# untitled6.net
KiCad netlist of a schematic drawn in EAGLE
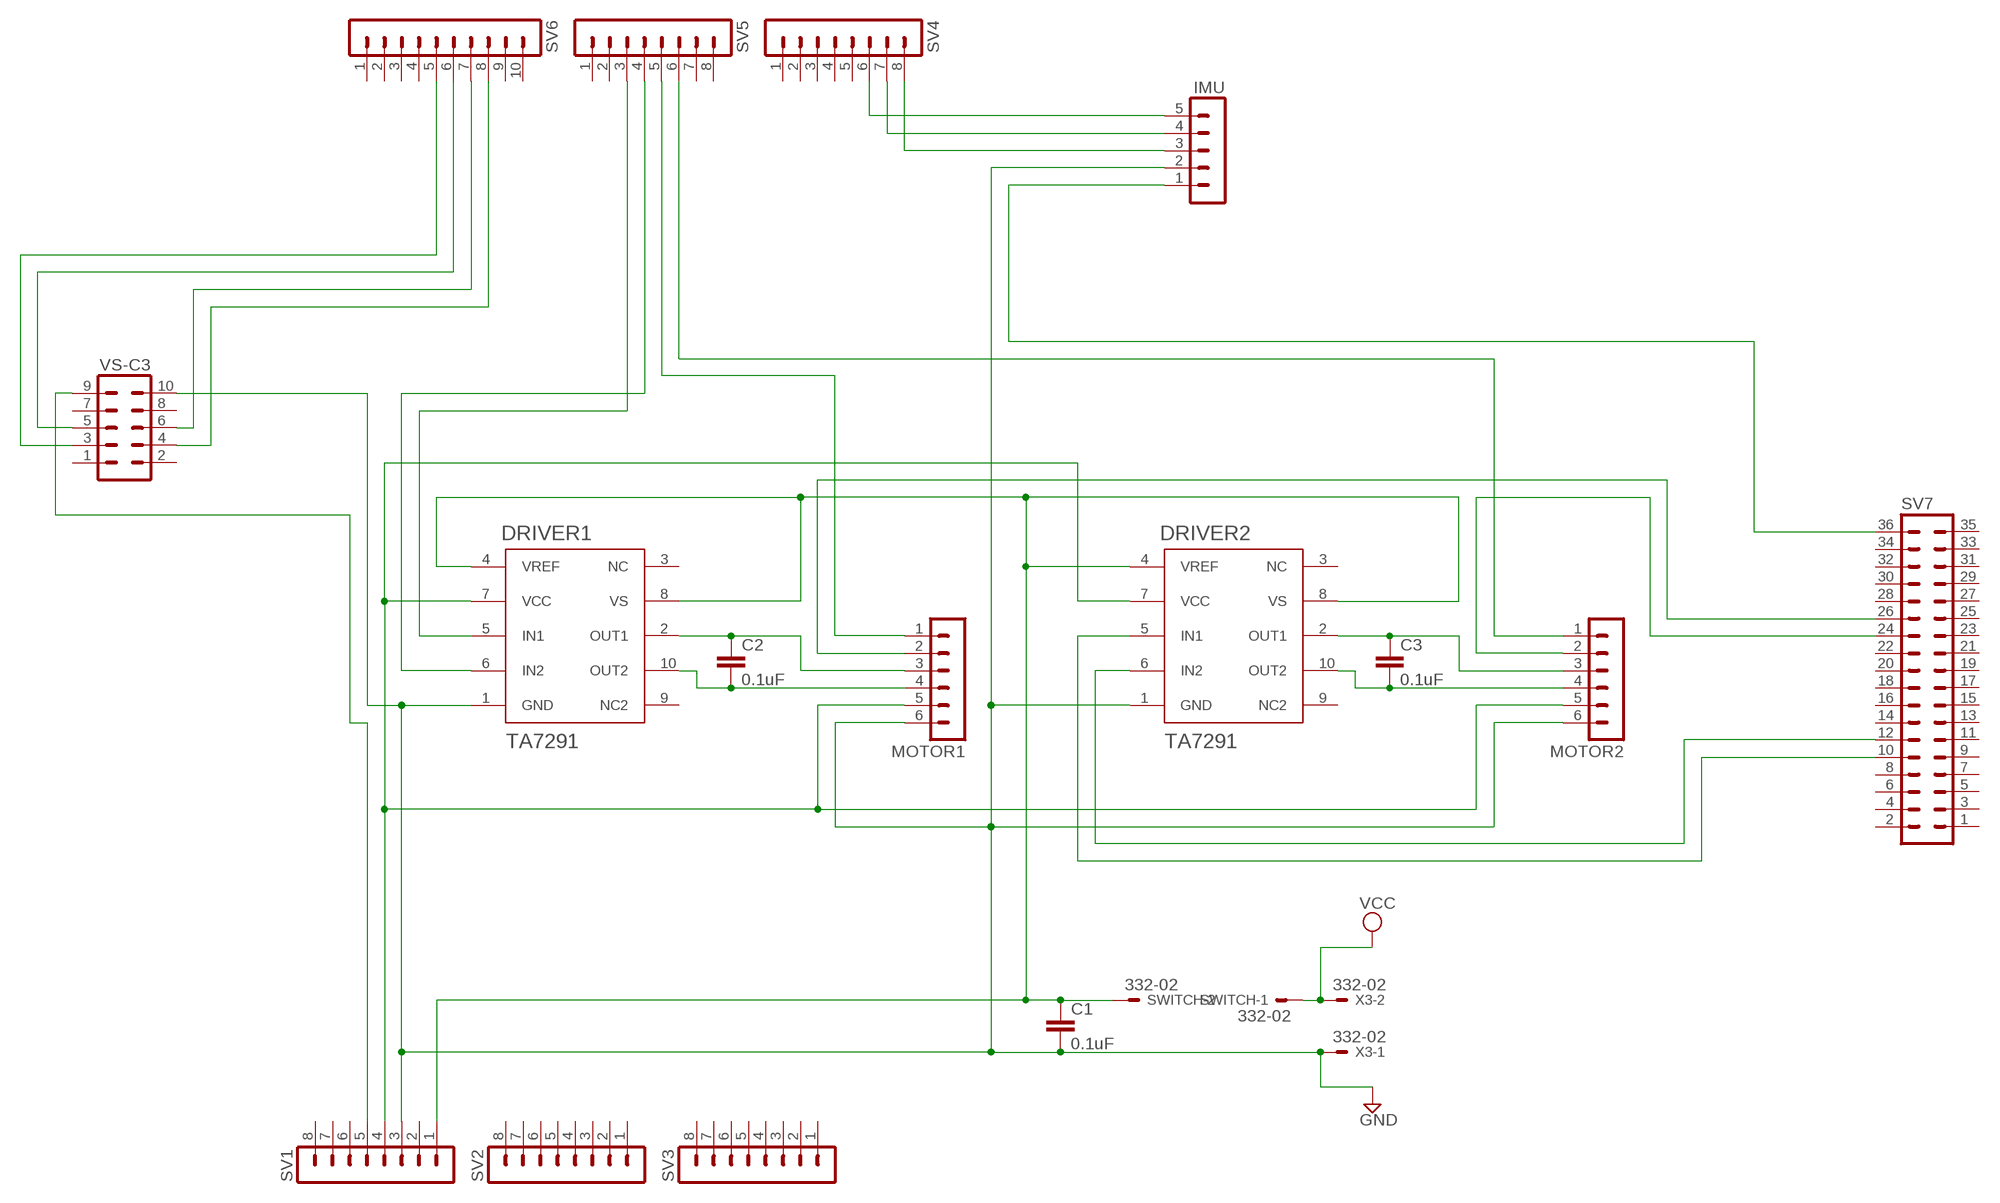
[diagram p0: schematic, sheet 1]

(export (version "E")
  (design (tool "Eeschema 10.0.6"))
  (components
    (comp (ref "C1")
      (value "0.1uF")
      (footprint "eagle-import:C5B2.5")
      (libsource (lib "eagle-import") (part "C5/2.5"))
    )
    (comp (ref "C2")
      (value "0.1uF")
      (footprint "eagle-import:C5B2.5")
      (libsource (lib "eagle-import") (part "C5/2.5"))
    )
    (comp (ref "C3")
      (value "0.1uF")
      (footprint "eagle-import:C5B2.5")
      (libsource (lib "eagle-import") (part "C5/2.5"))
    )
    (comp (ref "DRIVER1")
      (value "TA7291")
      (footprint "eagle-import:HSIP10")
      (libsource (lib "eagle-import") (part "TA7291"))
    )
    (comp (ref "DRIVER2")
      (value "TA7291")
      (footprint "eagle-import:HSIP10")
      (libsource (lib "eagle-import") (part "TA7291"))
    )
    (comp (ref "IMU")
      (value "MA05-1")
      (footprint "eagle-import:MA05-1")
      (libsource (lib "eagle-import") (part "MA05-1"))
    )
    (comp (ref "MOTOR1")
      (value "MA06-1")
      (footprint "eagle-import:MA06-1")
      (libsource (lib "eagle-import") (part "MA06-1"))
    )
    (comp (ref "MOTOR2")
      (value "MA06-1")
      (footprint "eagle-import:MA06-1")
      (libsource (lib "eagle-import") (part "MA06-1"))
    )
    (comp (ref "SV1")
      (value "MA08-1")
      (footprint "eagle-import:MA08-1")
      (libsource (lib "eagle-import") (part "MA08-1"))
    )
    (comp (ref "SV2")
      (value "MA08-1")
      (footprint "eagle-import:MA08-1")
      (libsource (lib "eagle-import") (part "MA08-1"))
    )
    (comp (ref "SV3")
      (value "MA08-1")
      (footprint "eagle-import:MA08-1")
      (libsource (lib "eagle-import") (part "MA08-1"))
    )
    (comp (ref "SV4")
      (value "MA08-1")
      (footprint "eagle-import:MA08-1")
      (libsource (lib "eagle-import") (part "MA08-1"))
    )
    (comp (ref "SV5")
      (value "MA08-1")
      (footprint "eagle-import:MA08-1")
      (libsource (lib "eagle-import") (part "MA08-1"))
    )
    (comp (ref "SV6")
      (value "MA10-1")
      (footprint "eagle-import:MA10-1")
      (libsource (lib "eagle-import") (part "MA10-1"))
    )
    (comp (ref "SV7")
      (value "MA18-2")
      (footprint "eagle-import:MA18-2")
      (libsource (lib "eagle-import") (part "MA18-2"))
    )
    (comp (ref "SWITCH")
      (value "332-02")
      (footprint "eagle-import:332-02")
      (libsource (lib "eagle-import") (part "332-02"))
    )
    (comp (ref "VS-C3")
      (value "MA05-2")
      (footprint "eagle-import:MA05-2")
      (libsource (lib "eagle-import") (part "MA05-2"))
    )
    (comp (ref "X3")
      (value "332-02")
      (footprint "eagle-import:332-02")
      (libsource (lib "eagle-import") (part "332-02"))
    )
  )
  (nets
    (net (code "1") (name "GND") (class "Default")
      (node (ref "C1") (pin "2") (pinfunction "2_2") (pintype "passive"))
      (node (ref "DRIVER1") (pin "1") (pinfunction "GND_1") (pintype "bidirectional"))
      (node (ref "DRIVER2") (pin "1") (pinfunction "GND_1") (pintype "bidirectional"))
      (node (ref "IMU") (pin "2") (pinfunction "2_2") (pintype "passive"))
      (node (ref "MOTOR1") (pin "6") (pinfunction "6_6") (pintype "passive"))
      (node (ref "MOTOR2") (pin "6") (pinfunction "6_6") (pintype "passive"))
      (node (ref "SV1") (pin "3") (pinfunction "3_3") (pintype "passive"))
      (node (ref "VS-C3") (pin "10") (pinfunction "10_10") (pintype "passive"))
      (node (ref "X3") (pin "1") (pinfunction "S_1") (pintype "passive"))
    )
    (net (code "2") (name "Net-(DRIVER1-IN1)") (class "Default")
      (node (ref "DRIVER1") (pin "5") (pinfunction "IN1_5") (pintype "bidirectional"))
      (node (ref "SV5") (pin "3") (pinfunction "3_3") (pintype "passive"))
    )
    (net (code "3") (name "Net-(DRIVER1-IN2)") (class "Default")
      (node (ref "DRIVER1") (pin "6") (pinfunction "IN2_6") (pintype "bidirectional"))
      (node (ref "SV5") (pin "4") (pinfunction "4_4") (pintype "passive"))
    )
    (net (code "4") (name "Net-(DRIVER1-OUT1)") (class "Default")
      (node (ref "C2") (pin "1") (pinfunction "1_1") (pintype "passive"))
      (node (ref "DRIVER1") (pin "2") (pinfunction "OUT1_2") (pintype "bidirectional"))
      (node (ref "MOTOR1") (pin "3") (pinfunction "3_3") (pintype "passive"))
    )
    (net (code "5") (name "Net-(DRIVER1-OUT2)") (class "Default")
      (node (ref "C2") (pin "2") (pinfunction "2_2") (pintype "passive"))
      (node (ref "DRIVER1") (pin "10") (pinfunction "OUT2_10") (pintype "bidirectional"))
      (node (ref "MOTOR1") (pin "4") (pinfunction "4_4") (pintype "passive"))
    )
    (net (code "6") (name "Net-(DRIVER1-VCC)") (class "Default")
      (node (ref "DRIVER1") (pin "7") (pinfunction "VCC_7") (pintype "bidirectional"))
      (node (ref "DRIVER2") (pin "7") (pinfunction "VCC_7") (pintype "bidirectional"))
      (node (ref "MOTOR1") (pin "5") (pinfunction "5_5") (pintype "passive"))
      (node (ref "MOTOR2") (pin "5") (pinfunction "5_5") (pintype "passive"))
      (node (ref "SV1") (pin "4") (pinfunction "4_4") (pintype "passive"))
    )
    (net (code "7") (name "Net-(DRIVER1-VREF)") (class "Default")
      (node (ref "C1") (pin "1") (pinfunction "1_1") (pintype "passive"))
      (node (ref "DRIVER1") (pin "4") (pinfunction "VREF_4") (pintype "bidirectional"))
      (node (ref "DRIVER1") (pin "8") (pinfunction "VS_8") (pintype "bidirectional"))
      (node (ref "DRIVER2") (pin "4") (pinfunction "VREF_4") (pintype "bidirectional"))
      (node (ref "DRIVER2") (pin "8") (pinfunction "VS_8") (pintype "bidirectional"))
      (node (ref "SV1") (pin "1") (pinfunction "1_1") (pintype "passive"))
      (node (ref "SWITCH") (pin "2") (pinfunction "S_2") (pintype "passive"))
    )
    (net (code "8") (name "Net-(DRIVER2-IN1)") (class "Default")
      (node (ref "DRIVER2") (pin "5") (pinfunction "IN1_5") (pintype "bidirectional"))
      (node (ref "SV7") (pin "10") (pinfunction "10_10") (pintype "passive"))
    )
    (net (code "9") (name "Net-(DRIVER2-IN2)") (class "Default")
      (node (ref "DRIVER2") (pin "6") (pinfunction "IN2_6") (pintype "bidirectional"))
      (node (ref "SV7") (pin "12") (pinfunction "12_12") (pintype "passive"))
    )
    (net (code "10") (name "Net-(DRIVER2-OUT1)") (class "Default")
      (node (ref "C3") (pin "1") (pinfunction "1_1") (pintype "passive"))
      (node (ref "DRIVER2") (pin "2") (pinfunction "OUT1_2") (pintype "bidirectional"))
      (node (ref "MOTOR2") (pin "3") (pinfunction "3_3") (pintype "passive"))
    )
    (net (code "11") (name "Net-(DRIVER2-OUT2)") (class "Default")
      (node (ref "C3") (pin "2") (pinfunction "2_2") (pintype "passive"))
      (node (ref "DRIVER2") (pin "10") (pinfunction "OUT2_10") (pintype "bidirectional"))
      (node (ref "MOTOR2") (pin "4") (pinfunction "4_4") (pintype "passive"))
    )
    (net (code "12") (name "Net-(IMU-Pad1)") (class "Default")
      (node (ref "IMU") (pin "1") (pinfunction "1_1") (pintype "passive"))
      (node (ref "SV7") (pin "36") (pinfunction "36_36") (pintype "passive"))
    )
    (net (code "13") (name "Net-(IMU-Pad3)") (class "Default")
      (node (ref "IMU") (pin "3") (pinfunction "3_3") (pintype "passive"))
      (node (ref "SV4") (pin "8") (pinfunction "8_8") (pintype "passive"))
    )
    (net (code "14") (name "Net-(IMU-Pad4)") (class "Default")
      (node (ref "IMU") (pin "4") (pinfunction "4_4") (pintype "passive"))
      (node (ref "SV4") (pin "7") (pinfunction "7_7") (pintype "passive"))
    )
    (net (code "15") (name "Net-(IMU-Pad5)") (class "Default")
      (node (ref "IMU") (pin "5") (pinfunction "5_5") (pintype "passive"))
      (node (ref "SV4") (pin "6") (pinfunction "6_6") (pintype "passive"))
    )
    (net (code "16") (name "Net-(MOTOR1-Pad1)") (class "Default")
      (node (ref "MOTOR1") (pin "1") (pinfunction "1_1") (pintype "passive"))
      (node (ref "SV5") (pin "5") (pinfunction "5_5") (pintype "passive"))
    )
    (net (code "17") (name "Net-(MOTOR1-Pad2)") (class "Default")
      (node (ref "MOTOR1") (pin "2") (pinfunction "2_2") (pintype "passive"))
      (node (ref "SV7") (pin "26") (pinfunction "26_26") (pintype "passive"))
    )
    (net (code "18") (name "Net-(MOTOR2-Pad1)") (class "Default")
      (node (ref "MOTOR2") (pin "1") (pinfunction "1_1") (pintype "passive"))
      (node (ref "SV5") (pin "6") (pinfunction "6_6") (pintype "passive"))
    )
    (net (code "19") (name "Net-(MOTOR2-Pad2)") (class "Default")
      (node (ref "MOTOR2") (pin "2") (pinfunction "2_2") (pintype "passive"))
      (node (ref "SV7") (pin "24") (pinfunction "24_24") (pintype "passive"))
    )
    (net (code "20") (name "Net-(SV1-Pad5)") (class "Default")
      (node (ref "SV1") (pin "5") (pinfunction "5_5") (pintype "passive"))
      (node (ref "VS-C3") (pin "9") (pinfunction "9_9") (pintype "passive"))
    )
    (net (code "21") (name "Net-(SV6-Pad5)") (class "Default")
      (node (ref "SV6") (pin "5") (pinfunction "5_5") (pintype "passive"))
      (node (ref "VS-C3") (pin "3") (pinfunction "3_3") (pintype "passive"))
    )
    (net (code "22") (name "Net-(SV6-Pad6)") (class "Default")
      (node (ref "SV6") (pin "6") (pinfunction "6_6") (pintype "passive"))
      (node (ref "VS-C3") (pin "5") (pinfunction "5_5") (pintype "passive"))
    )
    (net (code "23") (name "Net-(SV6-Pad7)") (class "Default")
      (node (ref "SV6") (pin "7") (pinfunction "7_7") (pintype "passive"))
      (node (ref "VS-C3") (pin "6") (pinfunction "6_6") (pintype "passive"))
    )
    (net (code "24") (name "Net-(SV6-Pad8)") (class "Default")
      (node (ref "SV6") (pin "8") (pinfunction "8_8") (pintype "passive"))
      (node (ref "VS-C3") (pin "4") (pinfunction "4_4") (pintype "passive"))
    )
    (net (code "25") (name "VCC") (class "Default")
      (node (ref "SWITCH") (pin "1") (pinfunction "S_1") (pintype "passive"))
      (node (ref "X3") (pin "2") (pinfunction "S_2") (pintype "passive"))
    )
    (net (code "26") (name "unconnected-(DRIVER1-NC-Pad3)") (class "Default")
      (node (ref "DRIVER1") (pin "3") (pinfunction "NC_3") (pintype "bidirectional"))
    )
    (net (code "27") (name "unconnected-(DRIVER1-NC2-Pad9)") (class "Default")
      (node (ref "DRIVER1") (pin "9") (pinfunction "NC2_9") (pintype "bidirectional"))
    )
    (net (code "28") (name "unconnected-(DRIVER2-NC-Pad3)") (class "Default")
      (node (ref "DRIVER2") (pin "3") (pinfunction "NC_3") (pintype "bidirectional"))
    )
    (net (code "29") (name "unconnected-(DRIVER2-NC2-Pad9)") (class "Default")
      (node (ref "DRIVER2") (pin "9") (pinfunction "NC2_9") (pintype "bidirectional"))
    )
    (net (code "30") (name "unconnected-(SV1-Pad2)") (class "Default")
      (node (ref "SV1") (pin "2") (pinfunction "2_2") (pintype "passive"))
    )
    (net (code "31") (name "unconnected-(SV1-Pad6)") (class "Default")
      (node (ref "SV1") (pin "6") (pinfunction "6_6") (pintype "passive"))
    )
    (net (code "32") (name "unconnected-(SV1-Pad7)") (class "Default")
      (node (ref "SV1") (pin "7") (pinfunction "7_7") (pintype "passive"))
    )
    (net (code "33") (name "unconnected-(SV1-Pad8)") (class "Default")
      (node (ref "SV1") (pin "8") (pinfunction "8_8") (pintype "passive"))
    )
    (net (code "34") (name "unconnected-(SV2-Pad1)") (class "Default")
      (node (ref "SV2") (pin "1") (pinfunction "1_1") (pintype "passive"))
    )
    (net (code "35") (name "unconnected-(SV2-Pad2)") (class "Default")
      (node (ref "SV2") (pin "2") (pinfunction "2_2") (pintype "passive"))
    )
    (net (code "36") (name "unconnected-(SV2-Pad3)") (class "Default")
      (node (ref "SV2") (pin "3") (pinfunction "3_3") (pintype "passive"))
    )
    (net (code "37") (name "unconnected-(SV2-Pad4)") (class "Default")
      (node (ref "SV2") (pin "4") (pinfunction "4_4") (pintype "passive"))
    )
    (net (code "38") (name "unconnected-(SV2-Pad5)") (class "Default")
      (node (ref "SV2") (pin "5") (pinfunction "5_5") (pintype "passive"))
    )
    (net (code "39") (name "unconnected-(SV2-Pad6)") (class "Default")
      (node (ref "SV2") (pin "6") (pinfunction "6_6") (pintype "passive"))
    )
    (net (code "40") (name "unconnected-(SV2-Pad7)") (class "Default")
      (node (ref "SV2") (pin "7") (pinfunction "7_7") (pintype "passive"))
    )
    (net (code "41") (name "unconnected-(SV2-Pad8)") (class "Default")
      (node (ref "SV2") (pin "8") (pinfunction "8_8") (pintype "passive"))
    )
    (net (code "42") (name "unconnected-(SV3-Pad1)") (class "Default")
      (node (ref "SV3") (pin "1") (pinfunction "1_1") (pintype "passive"))
    )
    (net (code "43") (name "unconnected-(SV3-Pad2)") (class "Default")
      (node (ref "SV3") (pin "2") (pinfunction "2_2") (pintype "passive"))
    )
    (net (code "44") (name "unconnected-(SV3-Pad3)") (class "Default")
      (node (ref "SV3") (pin "3") (pinfunction "3_3") (pintype "passive"))
    )
    (net (code "45") (name "unconnected-(SV3-Pad4)") (class "Default")
      (node (ref "SV3") (pin "4") (pinfunction "4_4") (pintype "passive"))
    )
    (net (code "46") (name "unconnected-(SV3-Pad5)") (class "Default")
      (node (ref "SV3") (pin "5") (pinfunction "5_5") (pintype "passive"))
    )
    (net (code "47") (name "unconnected-(SV3-Pad6)") (class "Default")
      (node (ref "SV3") (pin "6") (pinfunction "6_6") (pintype "passive"))
    )
    (net (code "48") (name "unconnected-(SV3-Pad7)") (class "Default")
      (node (ref "SV3") (pin "7") (pinfunction "7_7") (pintype "passive"))
    )
    (net (code "49") (name "unconnected-(SV3-Pad8)") (class "Default")
      (node (ref "SV3") (pin "8") (pinfunction "8_8") (pintype "passive"))
    )
    (net (code "50") (name "unconnected-(SV4-Pad1)") (class "Default")
      (node (ref "SV4") (pin "1") (pinfunction "1_1") (pintype "passive"))
    )
    (net (code "51") (name "unconnected-(SV4-Pad2)") (class "Default")
      (node (ref "SV4") (pin "2") (pinfunction "2_2") (pintype "passive"))
    )
    (net (code "52") (name "unconnected-(SV4-Pad3)") (class "Default")
      (node (ref "SV4") (pin "3") (pinfunction "3_3") (pintype "passive"))
    )
    (net (code "53") (name "unconnected-(SV4-Pad4)") (class "Default")
      (node (ref "SV4") (pin "4") (pinfunction "4_4") (pintype "passive"))
    )
    (net (code "54") (name "unconnected-(SV4-Pad5)") (class "Default")
      (node (ref "SV4") (pin "5") (pinfunction "5_5") (pintype "passive"))
    )
    (net (code "55") (name "unconnected-(SV5-Pad1)") (class "Default")
      (node (ref "SV5") (pin "1") (pinfunction "1_1") (pintype "passive"))
    )
    (net (code "56") (name "unconnected-(SV5-Pad2)") (class "Default")
      (node (ref "SV5") (pin "2") (pinfunction "2_2") (pintype "passive"))
    )
    (net (code "57") (name "unconnected-(SV5-Pad7)") (class "Default")
      (node (ref "SV5") (pin "7") (pinfunction "7_7") (pintype "passive"))
    )
    (net (code "58") (name "unconnected-(SV5-Pad8)") (class "Default")
      (node (ref "SV5") (pin "8") (pinfunction "8_8") (pintype "passive"))
    )
    (net (code "59") (name "unconnected-(SV6-Pad1)") (class "Default")
      (node (ref "SV6") (pin "1") (pinfunction "1_1") (pintype "passive"))
    )
    (net (code "60") (name "unconnected-(SV6-Pad2)") (class "Default")
      (node (ref "SV6") (pin "2") (pinfunction "2_2") (pintype "passive"))
    )
    (net (code "61") (name "unconnected-(SV6-Pad3)") (class "Default")
      (node (ref "SV6") (pin "3") (pinfunction "3_3") (pintype "passive"))
    )
    (net (code "62") (name "unconnected-(SV6-Pad4)") (class "Default")
      (node (ref "SV6") (pin "4") (pinfunction "4_4") (pintype "passive"))
    )
    (net (code "63") (name "unconnected-(SV6-Pad9)") (class "Default")
      (node (ref "SV6") (pin "9") (pinfunction "9_9") (pintype "passive"))
    )
    (net (code "64") (name "unconnected-(SV6-Pad10)") (class "Default")
      (node (ref "SV6") (pin "10") (pinfunction "10_10") (pintype "passive"))
    )
    (net (code "65") (name "unconnected-(SV7-Pad1)") (class "Default")
      (node (ref "SV7") (pin "1") (pinfunction "1_1") (pintype "passive"))
    )
    (net (code "66") (name "unconnected-(SV7-Pad2)") (class "Default")
      (node (ref "SV7") (pin "2") (pinfunction "2_2") (pintype "passive"))
    )
    (net (code "67") (name "unconnected-(SV7-Pad3)") (class "Default")
      (node (ref "SV7") (pin "3") (pinfunction "3_3") (pintype "passive"))
    )
    (net (code "68") (name "unconnected-(SV7-Pad4)") (class "Default")
      (node (ref "SV7") (pin "4") (pinfunction "4_4") (pintype "passive"))
    )
    (net (code "69") (name "unconnected-(SV7-Pad5)") (class "Default")
      (node (ref "SV7") (pin "5") (pinfunction "5_5") (pintype "passive"))
    )
    (net (code "70") (name "unconnected-(SV7-Pad6)") (class "Default")
      (node (ref "SV7") (pin "6") (pinfunction "6_6") (pintype "passive"))
    )
    (net (code "71") (name "unconnected-(SV7-Pad7)") (class "Default")
      (node (ref "SV7") (pin "7") (pinfunction "7_7") (pintype "passive"))
    )
    (net (code "72") (name "unconnected-(SV7-Pad8)") (class "Default")
      (node (ref "SV7") (pin "8") (pinfunction "8_8") (pintype "passive"))
    )
    (net (code "73") (name "unconnected-(SV7-Pad9)") (class "Default")
      (node (ref "SV7") (pin "9") (pinfunction "9_9") (pintype "passive"))
    )
    (net (code "74") (name "unconnected-(SV7-Pad11)") (class "Default")
      (node (ref "SV7") (pin "11") (pinfunction "11_11") (pintype "passive"))
    )
    (net (code "75") (name "unconnected-(SV7-Pad13)") (class "Default")
      (node (ref "SV7") (pin "13") (pinfunction "13_13") (pintype "passive"))
    )
    (net (code "76") (name "unconnected-(SV7-Pad14)") (class "Default")
      (node (ref "SV7") (pin "14") (pinfunction "14_14") (pintype "passive"))
    )
    (net (code "77") (name "unconnected-(SV7-Pad15)") (class "Default")
      (node (ref "SV7") (pin "15") (pinfunction "15_15") (pintype "passive"))
    )
    (net (code "78") (name "unconnected-(SV7-Pad16)") (class "Default")
      (node (ref "SV7") (pin "16") (pinfunction "16_16") (pintype "passive"))
    )
    (net (code "79") (name "unconnected-(SV7-Pad17)") (class "Default")
      (node (ref "SV7") (pin "17") (pinfunction "17_17") (pintype "passive"))
    )
    (net (code "80") (name "unconnected-(SV7-Pad18)") (class "Default")
      (node (ref "SV7") (pin "18") (pinfunction "18_18") (pintype "passive"))
    )
    (net (code "81") (name "unconnected-(SV7-Pad19)") (class "Default")
      (node (ref "SV7") (pin "19") (pinfunction "19_19") (pintype "passive"))
    )
    (net (code "82") (name "unconnected-(SV7-Pad20)") (class "Default")
      (node (ref "SV7") (pin "20") (pinfunction "20_20") (pintype "passive"))
    )
    (net (code "83") (name "unconnected-(SV7-Pad21)") (class "Default")
      (node (ref "SV7") (pin "21") (pinfunction "21_21") (pintype "passive"))
    )
    (net (code "84") (name "unconnected-(SV7-Pad22)") (class "Default")
      (node (ref "SV7") (pin "22") (pinfunction "22_22") (pintype "passive"))
    )
    (net (code "85") (name "unconnected-(SV7-Pad23)") (class "Default")
      (node (ref "SV7") (pin "23") (pinfunction "23_23") (pintype "passive"))
    )
    (net (code "86") (name "unconnected-(SV7-Pad25)") (class "Default")
      (node (ref "SV7") (pin "25") (pinfunction "25_25") (pintype "passive"))
    )
    (net (code "87") (name "unconnected-(SV7-Pad27)") (class "Default")
      (node (ref "SV7") (pin "27") (pinfunction "27_27") (pintype "passive"))
    )
    (net (code "88") (name "unconnected-(SV7-Pad28)") (class "Default")
      (node (ref "SV7") (pin "28") (pinfunction "28_28") (pintype "passive"))
    )
    (net (code "89") (name "unconnected-(SV7-Pad29)") (class "Default")
      (node (ref "SV7") (pin "29") (pinfunction "29_29") (pintype "passive"))
    )
    (net (code "90") (name "unconnected-(SV7-Pad30)") (class "Default")
      (node (ref "SV7") (pin "30") (pinfunction "30_30") (pintype "passive"))
    )
    (net (code "91") (name "unconnected-(SV7-Pad31)") (class "Default")
      (node (ref "SV7") (pin "31") (pinfunction "31_31") (pintype "passive"))
    )
    (net (code "92") (name "unconnected-(SV7-Pad32)") (class "Default")
      (node (ref "SV7") (pin "32") (pinfunction "32_32") (pintype "passive"))
    )
    (net (code "93") (name "unconnected-(SV7-Pad33)") (class "Default")
      (node (ref "SV7") (pin "33") (pinfunction "33_33") (pintype "passive"))
    )
    (net (code "94") (name "unconnected-(SV7-Pad34)") (class "Default")
      (node (ref "SV7") (pin "34") (pinfunction "34_34") (pintype "passive"))
    )
    (net (code "95") (name "unconnected-(SV7-Pad35)") (class "Default")
      (node (ref "SV7") (pin "35") (pinfunction "35_35") (pintype "passive"))
    )
    (net (code "96") (name "unconnected-(VS-C3-Pad1)") (class "Default")
      (node (ref "VS-C3") (pin "1") (pinfunction "1_1") (pintype "passive"))
    )
    (net (code "97") (name "unconnected-(VS-C3-Pad2)") (class "Default")
      (node (ref "VS-C3") (pin "2") (pinfunction "2_2") (pintype "passive"))
    )
    (net (code "98") (name "unconnected-(VS-C3-Pad7)") (class "Default")
      (node (ref "VS-C3") (pin "7") (pinfunction "7_7") (pintype "passive"))
    )
    (net (code "99") (name "unconnected-(VS-C3-Pad8)") (class "Default")
      (node (ref "VS-C3") (pin "8") (pinfunction "8_8") (pintype "passive"))
    )
  )
)
